# Z80RT.net
KiCad netlist of a schematic drawn in EAGLE
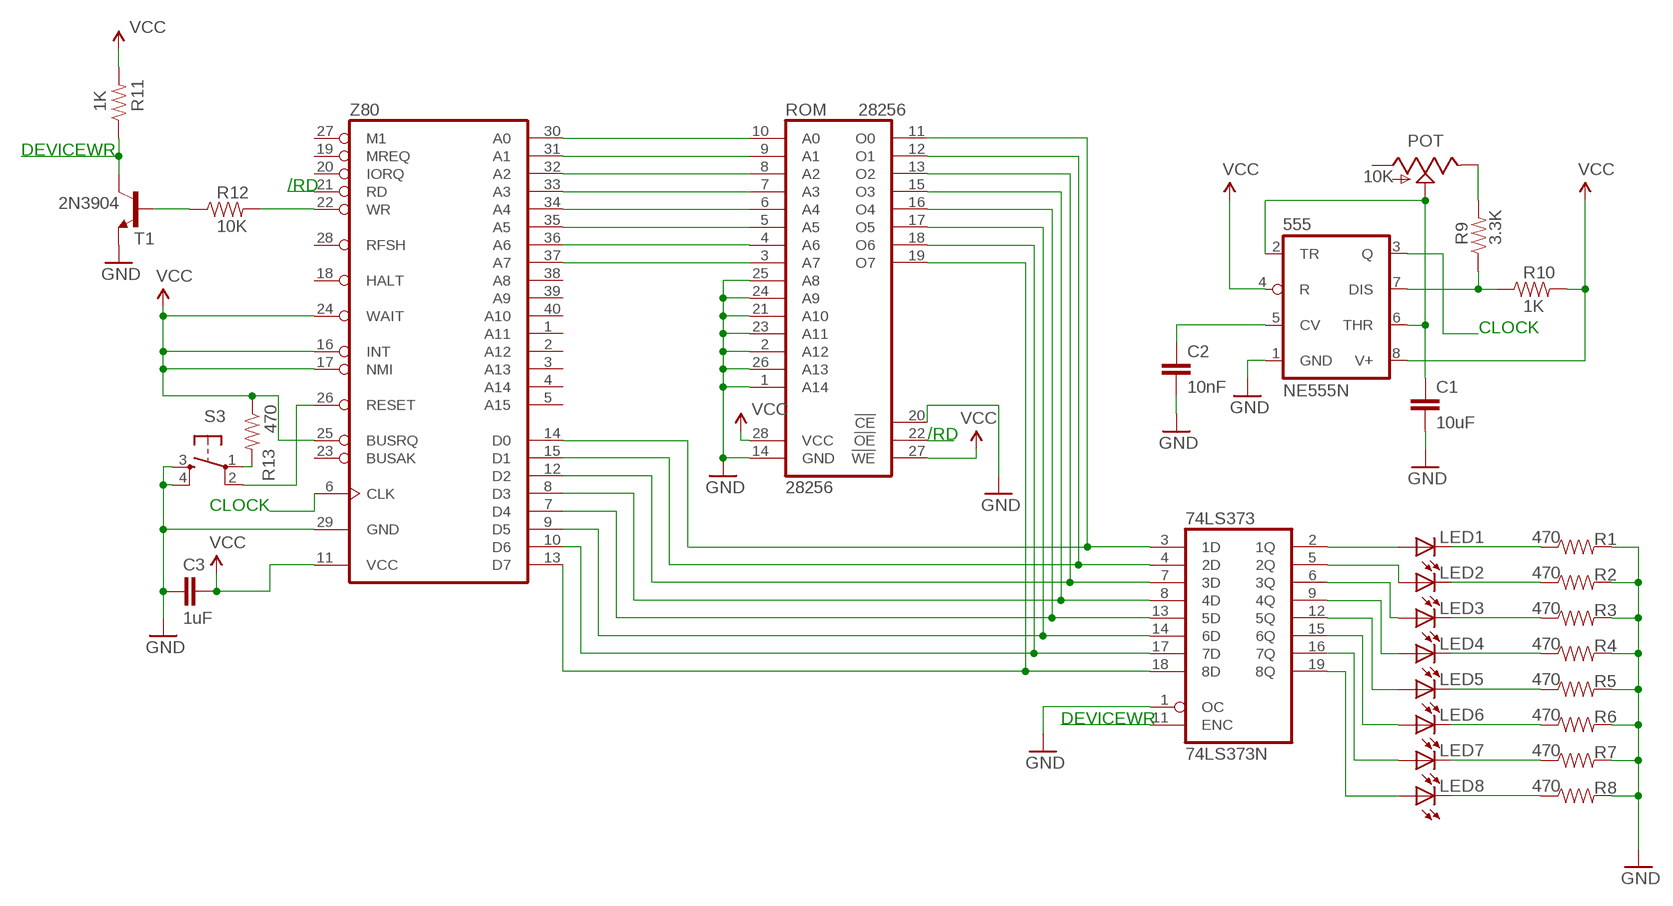
[diagram p0: schematic, sheet 1]

(export (version "E")
  (design (tool "Eeschema 10.0.6"))
  (components
    (comp (ref "74LS373")
      (value "74LS373N")
      (footprint "eagle-import:DIL20")
      (libsource (lib "eagle-import") (part "74373NLS"))
    )
    (comp (ref "555")
      (value "NE555N")
      (footprint "eagle-import:DIL08-ROUND")
      (libsource (lib "eagle-import") (part "555NNE"))
    )
    (comp (ref "C1")
      (value "10uF")
      (footprint "eagle-import:E5-5")
      (libsource (lib "eagle-import") (part "CAP"))
    )
    (comp (ref "C2")
      (value "10nF")
      (footprint "eagle-import:E5-5")
      (libsource (lib "eagle-import") (part "CAP"))
    )
    (comp (ref "C3")
      (value "1uF")
      (footprint "eagle-import:E5-5")
      (libsource (lib "eagle-import") (part "CAP"))
    )
    (comp (ref "LED1")
      (value "LED5MM")
      (footprint "eagle-import:LED5MM")
      (libsource (lib "eagle-import") (part "LED5MM"))
    )
    (comp (ref "LED2")
      (value "LED5MM")
      (footprint "eagle-import:LED5MM")
      (libsource (lib "eagle-import") (part "LED5MM"))
    )
    (comp (ref "LED3")
      (value "LED5MM")
      (footprint "eagle-import:LED5MM")
      (libsource (lib "eagle-import") (part "LED5MM"))
    )
    (comp (ref "LED4")
      (value "LED5MM")
      (footprint "eagle-import:LED5MM")
      (libsource (lib "eagle-import") (part "LED5MM"))
    )
    (comp (ref "LED5")
      (value "LED5MM")
      (footprint "eagle-import:LED5MM")
      (libsource (lib "eagle-import") (part "LED5MM"))
    )
    (comp (ref "LED6")
      (value "LED5MM")
      (footprint "eagle-import:LED5MM")
      (libsource (lib "eagle-import") (part "LED5MM"))
    )
    (comp (ref "LED7")
      (value "LED5MM")
      (footprint "eagle-import:LED5MM")
      (libsource (lib "eagle-import") (part "LED5MM"))
    )
    (comp (ref "LED8")
      (value "LED5MM")
      (footprint "eagle-import:LED5MM")
      (libsource (lib "eagle-import") (part "LED5MM"))
    )
    (comp (ref "POT")
      (value "10K")
      (footprint "eagle-import:POT_ALPHA_RV16AF-20")
      (libsource (lib "eagle-import") (part "POT-RV16AF-20"))
    )
    (comp (ref "R1")
      (value "470")
      (footprint "eagle-import:AXIAL-0.4")
      (libsource (lib "eagle-import") (part "RESISTORPTH-1/4W"))
    )
    (comp (ref "R2")
      (value "470")
      (footprint "eagle-import:AXIAL-0.4")
      (libsource (lib "eagle-import") (part "RESISTORPTH-1/4W"))
    )
    (comp (ref "R3")
      (value "470")
      (footprint "eagle-import:AXIAL-0.4")
      (libsource (lib "eagle-import") (part "RESISTORPTH-1/4W"))
    )
    (comp (ref "R4")
      (value "470")
      (footprint "eagle-import:AXIAL-0.4")
      (libsource (lib "eagle-import") (part "RESISTORPTH-1/4W"))
    )
    (comp (ref "R5")
      (value "470")
      (footprint "eagle-import:AXIAL-0.4")
      (libsource (lib "eagle-import") (part "RESISTORPTH-1/4W"))
    )
    (comp (ref "R6")
      (value "470")
      (footprint "eagle-import:AXIAL-0.4")
      (libsource (lib "eagle-import") (part "RESISTORPTH-1/4W"))
    )
    (comp (ref "R7")
      (value "470")
      (footprint "eagle-import:AXIAL-0.4")
      (libsource (lib "eagle-import") (part "RESISTORPTH-1/4W"))
    )
    (comp (ref "R8")
      (value "470")
      (footprint "eagle-import:AXIAL-0.4")
      (libsource (lib "eagle-import") (part "RESISTORPTH-1/4W"))
    )
    (comp (ref "R9")
      (value "3.3K")
      (footprint "eagle-import:AXIAL-0.4")
      (libsource (lib "eagle-import") (part "RESISTORPTH-1/4W"))
    )
    (comp (ref "R10")
      (value "1K")
      (footprint "eagle-import:AXIAL-0.4")
      (libsource (lib "eagle-import") (part "RESISTORPTH-1/4W"))
    )
    (comp (ref "R11")
      (value "1K")
      (footprint "eagle-import:AXIAL-0.4")
      (libsource (lib "eagle-import") (part "RESISTORPTH-1/4W"))
    )
    (comp (ref "R12")
      (value "10K")
      (footprint "eagle-import:AXIAL-0.4")
      (libsource (lib "eagle-import") (part "RESISTORPTH-1/4W"))
    )
    (comp (ref "R13")
      (value "470")
      (footprint "eagle-import:AXIAL-0.4")
      (libsource (lib "eagle-import") (part "RESISTORPTH-1/4W"))
    )
    (comp (ref "ROM")
      (value "28256")
      (footprint "eagle-import:DIL28")
      (libsource (lib "eagle-import") (part "28256"))
    )
    (comp (ref "S3")
      (value "TAC_SWITCHPTH")
      (footprint "eagle-import:TACTILE-PTH")
      (libsource (lib "eagle-import") (part "TAC_SWITCHPTH"))
    )
    (comp (ref "T1")
      (value "2N3904")
      (footprint "eagle-import:TO92")
      (libsource (lib "eagle-import") (part "2N3904"))
    )
    (comp (ref "Z80")
      (value "Z80CPU")
      (footprint "eagle-import:DIL40")
      (libsource (lib "eagle-import") (part "Z80CPU"))
    )
  )
  (nets
    (net (code "1") (name "/CLOCK") (class "Default")
      (node (ref "555") (pin "3") (pinfunction "Q_3") (pintype "output"))
      (node (ref "Z80") (pin "6") (pinfunction "CLK_6") (pintype "input"))
    )
    (net (code "2") (name "/DEVICEWR") (class "Default")
      (node (ref "74LS373") (pin "11") (pinfunction "ENC_11") (pintype "input"))
      (node (ref "R11") (pin "P$1") (pinfunction "1_P$1") (pintype "passive"))
      (node (ref "T1") (pin "1") (pinfunction "C_1") (pintype "passive"))
    )
    (net (code "3") (name "/{slash}RD") (class "Default")
      (node (ref "ROM") (pin "22") (pinfunction "~{OE}_22") (pintype "input"))
      (node (ref "Z80") (pin "21") (pinfunction "RD_21") (pintype "output"))
    )
    (net (code "4") (name "GND") (class "Default")
      (node (ref "555") (pin "1") (pinfunction "GND_1") (pintype "power_in"))
      (node (ref "74LS373") (pin "1") (pinfunction "OC_1") (pintype "input"))
      (node (ref "C1") (pin "-") (pinfunction "2_-") (pintype "passive"))
      (node (ref "C2") (pin "-") (pinfunction "2_-") (pintype "passive"))
      (node (ref "C3") (pin "-") (pinfunction "2_-") (pintype "passive"))
      (node (ref "R1") (pin "P$2") (pinfunction "2_P$2") (pintype "passive"))
      (node (ref "R2") (pin "P$2") (pinfunction "2_P$2") (pintype "passive"))
      (node (ref "R3") (pin "P$2") (pinfunction "2_P$2") (pintype "passive"))
      (node (ref "R4") (pin "P$2") (pinfunction "2_P$2") (pintype "passive"))
      (node (ref "R5") (pin "P$2") (pinfunction "2_P$2") (pintype "passive"))
      (node (ref "R6") (pin "P$2") (pinfunction "2_P$2") (pintype "passive"))
      (node (ref "R7") (pin "P$2") (pinfunction "2_P$2") (pintype "passive"))
      (node (ref "R8") (pin "P$2") (pinfunction "2_P$2") (pintype "passive"))
      (node (ref "ROM") (pin "1") (pinfunction "A14_1") (pintype "input"))
      (node (ref "ROM") (pin "14") (pinfunction "GND_14") (pintype "tri_state"))
      (node (ref "ROM") (pin "2") (pinfunction "A12_2") (pintype "input"))
      (node (ref "ROM") (pin "20") (pinfunction "~{CE}_20") (pintype "input"))
      (node (ref "ROM") (pin "21") (pinfunction "A10_21") (pintype "input"))
      (node (ref "ROM") (pin "23") (pinfunction "A11_23") (pintype "input"))
      (node (ref "ROM") (pin "24") (pinfunction "A9_24") (pintype "input"))
      (node (ref "ROM") (pin "25") (pinfunction "A8_25") (pintype "input"))
      (node (ref "ROM") (pin "26") (pinfunction "A13_26") (pintype "input"))
      (node (ref "S3") (pin "3") (pinfunction "3_3") (pintype "passive"))
      (node (ref "S3") (pin "4") (pinfunction "4_4") (pintype "passive"))
      (node (ref "T1") (pin "3") (pinfunction "E_3") (pintype "passive"))
      (node (ref "Z80") (pin "29") (pinfunction "GND_29") (pintype "power_in"))
    )
    (net (code "5") (name "Net-(74LS373A-1D)") (class "Default")
      (node (ref "74LS373") (pin "3") (pinfunction "1D_3") (pintype "input"))
      (node (ref "ROM") (pin "11") (pinfunction "O0_11") (pintype "tri_state"))
      (node (ref "Z80") (pin "14") (pinfunction "D0_14") (pintype "bidirectional"))
    )
    (net (code "6") (name "Net-(74LS373A-1Q)") (class "Default")
      (node (ref "74LS373") (pin "2") (pinfunction "1Q_2") (pintype "tri_state"))
      (node (ref "LED1") (pin "A") (pinfunction "A_A") (pintype "passive"))
    )
    (net (code "7") (name "Net-(74LS373A-2D)") (class "Default")
      (node (ref "74LS373") (pin "4") (pinfunction "2D_4") (pintype "input"))
      (node (ref "ROM") (pin "12") (pinfunction "O1_12") (pintype "tri_state"))
      (node (ref "Z80") (pin "15") (pinfunction "D1_15") (pintype "bidirectional"))
    )
    (net (code "8") (name "Net-(74LS373A-2Q)") (class "Default")
      (node (ref "74LS373") (pin "5") (pinfunction "2Q_5") (pintype "tri_state"))
      (node (ref "LED2") (pin "A") (pinfunction "A_A") (pintype "passive"))
    )
    (net (code "9") (name "Net-(74LS373A-3D)") (class "Default")
      (node (ref "74LS373") (pin "7") (pinfunction "3D_7") (pintype "input"))
      (node (ref "ROM") (pin "13") (pinfunction "O2_13") (pintype "tri_state"))
      (node (ref "Z80") (pin "12") (pinfunction "D2_12") (pintype "bidirectional"))
    )
    (net (code "10") (name "Net-(74LS373A-3Q)") (class "Default")
      (node (ref "74LS373") (pin "6") (pinfunction "3Q_6") (pintype "tri_state"))
      (node (ref "LED3") (pin "A") (pinfunction "A_A") (pintype "passive"))
    )
    (net (code "11") (name "Net-(74LS373A-4D)") (class "Default")
      (node (ref "74LS373") (pin "8") (pinfunction "4D_8") (pintype "input"))
      (node (ref "ROM") (pin "15") (pinfunction "O3_15") (pintype "tri_state"))
      (node (ref "Z80") (pin "8") (pinfunction "D3_8") (pintype "bidirectional"))
    )
    (net (code "12") (name "Net-(74LS373A-4Q)") (class "Default")
      (node (ref "74LS373") (pin "9") (pinfunction "4Q_9") (pintype "tri_state"))
      (node (ref "LED4") (pin "A") (pinfunction "A_A") (pintype "passive"))
    )
    (net (code "13") (name "Net-(74LS373A-5D)") (class "Default")
      (node (ref "74LS373") (pin "13") (pinfunction "5D_13") (pintype "input"))
      (node (ref "ROM") (pin "16") (pinfunction "O4_16") (pintype "tri_state"))
      (node (ref "Z80") (pin "7") (pinfunction "D4_7") (pintype "bidirectional"))
    )
    (net (code "14") (name "Net-(74LS373A-5Q)") (class "Default")
      (node (ref "74LS373") (pin "12") (pinfunction "5Q_12") (pintype "tri_state"))
      (node (ref "LED5") (pin "A") (pinfunction "A_A") (pintype "passive"))
    )
    (net (code "15") (name "Net-(74LS373A-6D)") (class "Default")
      (node (ref "74LS373") (pin "14") (pinfunction "6D_14") (pintype "input"))
      (node (ref "ROM") (pin "17") (pinfunction "O5_17") (pintype "tri_state"))
      (node (ref "Z80") (pin "9") (pinfunction "D5_9") (pintype "bidirectional"))
    )
    (net (code "16") (name "Net-(74LS373A-6Q)") (class "Default")
      (node (ref "74LS373") (pin "15") (pinfunction "6Q_15") (pintype "tri_state"))
      (node (ref "LED6") (pin "A") (pinfunction "A_A") (pintype "passive"))
    )
    (net (code "17") (name "Net-(74LS373A-7D)") (class "Default")
      (node (ref "74LS373") (pin "17") (pinfunction "7D_17") (pintype "input"))
      (node (ref "ROM") (pin "18") (pinfunction "O6_18") (pintype "tri_state"))
      (node (ref "Z80") (pin "10") (pinfunction "D6_10") (pintype "bidirectional"))
    )
    (net (code "18") (name "Net-(74LS373A-7Q)") (class "Default")
      (node (ref "74LS373") (pin "16") (pinfunction "7Q_16") (pintype "tri_state"))
      (node (ref "LED7") (pin "A") (pinfunction "A_A") (pintype "passive"))
    )
    (net (code "19") (name "Net-(74LS373A-8D)") (class "Default")
      (node (ref "74LS373") (pin "18") (pinfunction "8D_18") (pintype "input"))
      (node (ref "ROM") (pin "19") (pinfunction "O7_19") (pintype "tri_state"))
      (node (ref "Z80") (pin "13") (pinfunction "D7_13") (pintype "bidirectional"))
    )
    (net (code "20") (name "Net-(74LS373A-8Q)") (class "Default")
      (node (ref "74LS373") (pin "19") (pinfunction "8Q_19") (pintype "tri_state"))
      (node (ref "LED8") (pin "A") (pinfunction "A_A") (pintype "passive"))
    )
    (net (code "21") (name "Net-(555-CV)") (class "Default")
      (node (ref "555") (pin "5") (pinfunction "CV_5") (pintype "input"))
      (node (ref "C2") (pin "+") (pinfunction "1_+") (pintype "passive"))
    )
    (net (code "22") (name "Net-(555-DIS)") (class "Default")
      (node (ref "555") (pin "7") (pinfunction "DIS_7") (pintype "input"))
      (node (ref "R10") (pin "P$1") (pinfunction "1_P$1") (pintype "passive"))
      (node (ref "R9") (pin "P$1") (pinfunction "1_P$1") (pintype "passive"))
    )
    (net (code "23") (name "Net-(555-THR)") (class "Default")
      (node (ref "555") (pin "2") (pinfunction "TR_2") (pintype "input"))
      (node (ref "555") (pin "6") (pinfunction "THR_6") (pintype "input"))
      (node (ref "C1") (pin "+") (pinfunction "1_+") (pintype "passive"))
      (node (ref "POT") (pin "2") (pinfunction "S_2") (pintype "passive"))
    )
    (net (code "24") (name "Net-(LED1-C)") (class "Default")
      (node (ref "LED1") (pin "K") (pinfunction "C_K") (pintype "passive"))
      (node (ref "R1") (pin "P$1") (pinfunction "1_P$1") (pintype "passive"))
    )
    (net (code "25") (name "Net-(LED2-C)") (class "Default")
      (node (ref "LED2") (pin "K") (pinfunction "C_K") (pintype "passive"))
      (node (ref "R2") (pin "P$1") (pinfunction "1_P$1") (pintype "passive"))
    )
    (net (code "26") (name "Net-(LED3-C)") (class "Default")
      (node (ref "LED3") (pin "K") (pinfunction "C_K") (pintype "passive"))
      (node (ref "R3") (pin "P$1") (pinfunction "1_P$1") (pintype "passive"))
    )
    (net (code "27") (name "Net-(LED4-C)") (class "Default")
      (node (ref "LED4") (pin "K") (pinfunction "C_K") (pintype "passive"))
      (node (ref "R4") (pin "P$1") (pinfunction "1_P$1") (pintype "passive"))
    )
    (net (code "28") (name "Net-(LED5-C)") (class "Default")
      (node (ref "LED5") (pin "K") (pinfunction "C_K") (pintype "passive"))
      (node (ref "R5") (pin "P$1") (pinfunction "1_P$1") (pintype "passive"))
    )
    (net (code "29") (name "Net-(LED6-C)") (class "Default")
      (node (ref "LED6") (pin "K") (pinfunction "C_K") (pintype "passive"))
      (node (ref "R6") (pin "P$1") (pinfunction "1_P$1") (pintype "passive"))
    )
    (net (code "30") (name "Net-(LED7-C)") (class "Default")
      (node (ref "LED7") (pin "K") (pinfunction "C_K") (pintype "passive"))
      (node (ref "R7") (pin "P$1") (pinfunction "1_P$1") (pintype "passive"))
    )
    (net (code "31") (name "Net-(LED8-C)") (class "Default")
      (node (ref "LED8") (pin "K") (pinfunction "C_K") (pintype "passive"))
      (node (ref "R8") (pin "P$1") (pinfunction "1_P$1") (pintype "passive"))
    )
    (net (code "32") (name "Net-(POT-E)") (class "Default")
      (node (ref "POT") (pin "3") (pinfunction "E_3") (pintype "passive"))
      (node (ref "R9") (pin "P$2") (pinfunction "2_P$2") (pintype "passive"))
    )
    (net (code "33") (name "Net-(R12-1)") (class "Default")
      (node (ref "R12") (pin "P$1") (pinfunction "1_P$1") (pintype "passive"))
      (node (ref "T1") (pin "2") (pinfunction "B_2") (pintype "passive"))
    )
    (net (code "34") (name "Net-(R12-2)") (class "Default")
      (node (ref "R12") (pin "P$2") (pinfunction "2_P$2") (pintype "passive"))
      (node (ref "Z80") (pin "22") (pinfunction "WR_22") (pintype "output"))
    )
    (net (code "35") (name "Net-(R13-2)") (class "Default")
      (node (ref "R13") (pin "P$2") (pinfunction "2_P$2") (pintype "passive"))
      (node (ref "S3") (pin "1") (pinfunction "1_1") (pintype "passive"))
    )
    (net (code "36") (name "Net-(ROM-A0)") (class "Default")
      (node (ref "ROM") (pin "10") (pinfunction "A0_10") (pintype "input"))
      (node (ref "Z80") (pin "30") (pinfunction "A0_30") (pintype "output"))
    )
    (net (code "37") (name "Net-(ROM-A1)") (class "Default")
      (node (ref "ROM") (pin "9") (pinfunction "A1_9") (pintype "input"))
      (node (ref "Z80") (pin "31") (pinfunction "A1_31") (pintype "output"))
    )
    (net (code "38") (name "Net-(ROM-A2)") (class "Default")
      (node (ref "ROM") (pin "8") (pinfunction "A2_8") (pintype "input"))
      (node (ref "Z80") (pin "32") (pinfunction "A2_32") (pintype "output"))
    )
    (net (code "39") (name "Net-(ROM-A3)") (class "Default")
      (node (ref "ROM") (pin "7") (pinfunction "A3_7") (pintype "input"))
      (node (ref "Z80") (pin "33") (pinfunction "A3_33") (pintype "output"))
    )
    (net (code "40") (name "Net-(ROM-A4)") (class "Default")
      (node (ref "ROM") (pin "6") (pinfunction "A4_6") (pintype "input"))
      (node (ref "Z80") (pin "34") (pinfunction "A4_34") (pintype "output"))
    )
    (net (code "41") (name "Net-(ROM-A5)") (class "Default")
      (node (ref "ROM") (pin "5") (pinfunction "A5_5") (pintype "input"))
      (node (ref "Z80") (pin "35") (pinfunction "A5_35") (pintype "output"))
    )
    (net (code "42") (name "Net-(ROM-A6)") (class "Default")
      (node (ref "ROM") (pin "4") (pinfunction "A6_4") (pintype "input"))
      (node (ref "Z80") (pin "36") (pinfunction "A6_36") (pintype "output"))
    )
    (net (code "43") (name "Net-(ROM-A7)") (class "Default")
      (node (ref "ROM") (pin "3") (pinfunction "A7_3") (pintype "input"))
      (node (ref "Z80") (pin "37") (pinfunction "A7_37") (pintype "output"))
    )
    (net (code "44") (name "Net-(Z80-RESET)") (class "Default")
      (node (ref "S3") (pin "2") (pinfunction "2_2") (pintype "passive"))
      (node (ref "Z80") (pin "26") (pinfunction "RESET_26") (pintype "input"))
    )
    (net (code "45") (name "VCC") (class "Default")
      (node (ref "555") (pin "4") (pinfunction "R_4") (pintype "input"))
      (node (ref "555") (pin "8") (pinfunction "V+_8") (pintype "power_in"))
      (node (ref "C3") (pin "+") (pinfunction "1_+") (pintype "passive"))
      (node (ref "R10") (pin "P$2") (pinfunction "2_P$2") (pintype "passive"))
      (node (ref "R11") (pin "P$2") (pinfunction "2_P$2") (pintype "passive"))
      (node (ref "R13") (pin "P$1") (pinfunction "1_P$1") (pintype "passive"))
      (node (ref "ROM") (pin "27") (pinfunction "~{WE}_27") (pintype "input"))
      (node (ref "ROM") (pin "28") (pinfunction "VCC_28") (pintype "tri_state"))
      (node (ref "Z80") (pin "11") (pinfunction "VCC_11") (pintype "power_in"))
      (node (ref "Z80") (pin "16") (pinfunction "INT_16") (pintype "input"))
      (node (ref "Z80") (pin "17") (pinfunction "NMI_17") (pintype "input"))
      (node (ref "Z80") (pin "24") (pinfunction "WAIT_24") (pintype "input"))
      (node (ref "Z80") (pin "25") (pinfunction "BUSRQ_25") (pintype "input"))
    )
    (net (code "46") (name "unconnected-(POT-A-Pad1)") (class "Default")
      (node (ref "POT") (pin "1") (pinfunction "A_1") (pintype "passive"))
    )
    (net (code "47") (name "unconnected-(Z80-A8-Pad38)") (class "Default")
      (node (ref "Z80") (pin "38") (pinfunction "A8_38") (pintype "output"))
    )
    (net (code "48") (name "unconnected-(Z80-A9-Pad39)") (class "Default")
      (node (ref "Z80") (pin "39") (pinfunction "A9_39") (pintype "output"))
    )
    (net (code "49") (name "unconnected-(Z80-A10-Pad40)") (class "Default")
      (node (ref "Z80") (pin "40") (pinfunction "A10_40") (pintype "output"))
    )
    (net (code "50") (name "unconnected-(Z80-A11-Pad1)") (class "Default")
      (node (ref "Z80") (pin "1") (pinfunction "A11_1") (pintype "output"))
    )
    (net (code "51") (name "unconnected-(Z80-A12-Pad2)") (class "Default")
      (node (ref "Z80") (pin "2") (pinfunction "A12_2") (pintype "output"))
    )
    (net (code "52") (name "unconnected-(Z80-A13-Pad3)") (class "Default")
      (node (ref "Z80") (pin "3") (pinfunction "A13_3") (pintype "output"))
    )
    (net (code "53") (name "unconnected-(Z80-A14-Pad4)") (class "Default")
      (node (ref "Z80") (pin "4") (pinfunction "A14_4") (pintype "output"))
    )
    (net (code "54") (name "unconnected-(Z80-A15-Pad5)") (class "Default")
      (node (ref "Z80") (pin "5") (pinfunction "A15_5") (pintype "output"))
    )
    (net (code "55") (name "unconnected-(Z80-BUSAK-Pad23)") (class "Default")
      (node (ref "Z80") (pin "23") (pinfunction "BUSAK_23") (pintype "output"))
    )
    (net (code "56") (name "unconnected-(Z80-HALT-Pad18)") (class "Default")
      (node (ref "Z80") (pin "18") (pinfunction "HALT_18") (pintype "output"))
    )
    (net (code "57") (name "unconnected-(Z80-IORQ-Pad20)") (class "Default")
      (node (ref "Z80") (pin "20") (pinfunction "IORQ_20") (pintype "output"))
    )
    (net (code "58") (name "unconnected-(Z80-M1-Pad27)") (class "Default")
      (node (ref "Z80") (pin "27") (pinfunction "M1_27") (pintype "output"))
    )
    (net (code "59") (name "unconnected-(Z80-MREQ-Pad19)") (class "Default")
      (node (ref "Z80") (pin "19") (pinfunction "MREQ_19") (pintype "output"))
    )
    (net (code "60") (name "unconnected-(Z80-RFSH-Pad28)") (class "Default")
      (node (ref "Z80") (pin "28") (pinfunction "RFSH_28") (pintype "output"))
    )
  )
)
